# drv592.net
KiCad netlist of a schematic drawn in EAGLE
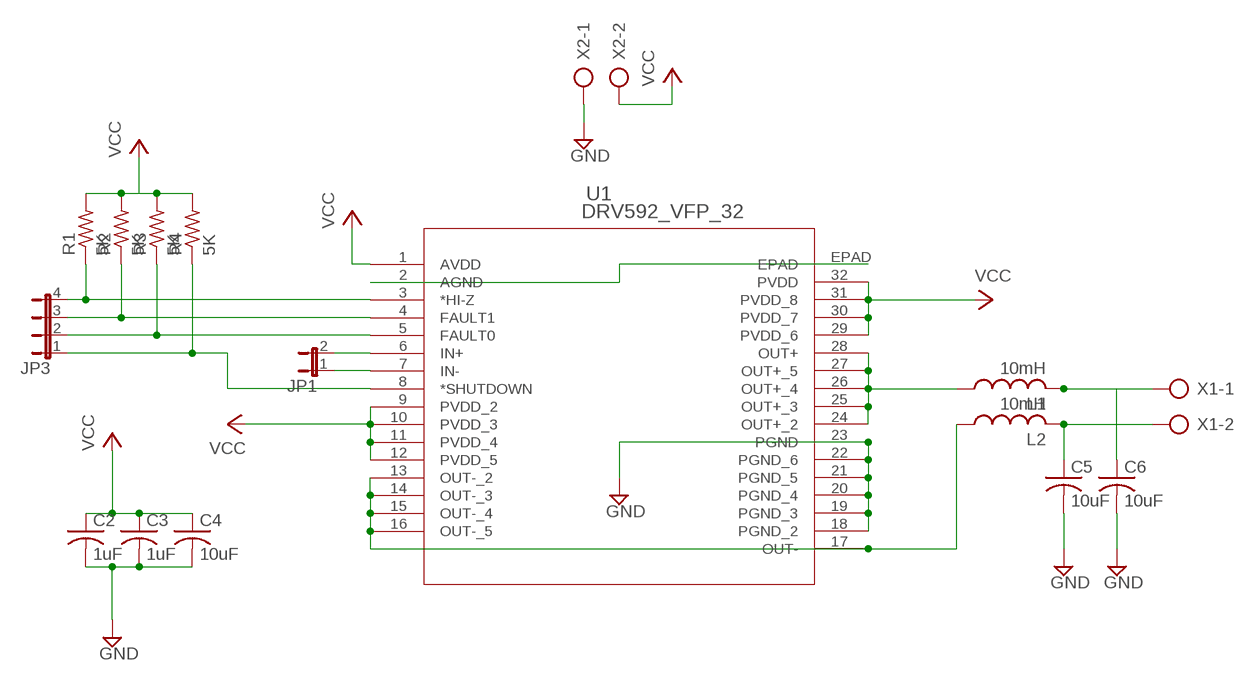
[diagram p0: schematic, sheet 1]

(export (version "E")
  (design (tool "Eeschema 10.0.6"))
  (components
    (comp (ref "C2")
      (value "1uF")
      (footprint "eagle-import:C050-030X075")
      (libsource (lib "eagle-import") (part "C-US050-030X075"))
    )
    (comp (ref "C3")
      (value "1uF")
      (footprint "eagle-import:C050-030X075")
      (libsource (lib "eagle-import") (part "C-US050-030X075"))
    )
    (comp (ref "C4")
      (value "10uF")
      (footprint "eagle-import:C050-030X075")
      (libsource (lib "eagle-import") (part "C-US050-030X075"))
    )
    (comp (ref "C5")
      (value "10uF")
      (footprint "eagle-import:C050-030X075")
      (libsource (lib "eagle-import") (part "C-US050-030X075"))
    )
    (comp (ref "C6")
      (value "10uF")
      (footprint "eagle-import:C050-030X075")
      (libsource (lib "eagle-import") (part "C-US050-030X075"))
    )
    (comp (ref "JP1")
      (value "JP1E")
      (footprint "eagle-import:JP1")
      (libsource (lib "eagle-import") (part "JP1E"))
    )
    (comp (ref "JP3")
      (value "JP4E")
      (footprint "eagle-import:JP4")
      (libsource (lib "eagle-import") (part "JP4E"))
    )
    (comp (ref "L1")
      (value "10mH")
      (footprint "eagle-import:TJ3-U2")
      (libsource (lib "eagle-import") (part "L-USTJ3-U2"))
    )
    (comp (ref "L2")
      (value "10mH")
      (footprint "eagle-import:TJ3-U2")
      (libsource (lib "eagle-import") (part "L-USTJ3-U2"))
    )
    (comp (ref "R1")
      (value "5K")
      (footprint "eagle-import:0207_10")
      (libsource (lib "eagle-import") (part "R-US_0207/10"))
    )
    (comp (ref "R2")
      (value "5K")
      (footprint "eagle-import:0207_10")
      (libsource (lib "eagle-import") (part "R-US_0207/10"))
    )
    (comp (ref "R3")
      (value "5K")
      (footprint "eagle-import:0207_10")
      (libsource (lib "eagle-import") (part "R-US_0207/10"))
    )
    (comp (ref "R4")
      (value "5K")
      (footprint "eagle-import:0207_10")
      (libsource (lib "eagle-import") (part "R-US_0207/10"))
    )
    (comp (ref "U1")
      (value "DRV592_VFP_32")
      (footprint "eagle-import:VFP32_3P91X3P91")
      (fields
        (field (name "GENERIC_PART_NUMBER") "DRV592")
        (field (name "MANUFACTURER") "Texas Instruments")
        (field (name "MANUFACTURER_PART_NUMBER") "drv592_vfp_32")
      )
      (libsource (lib "eagle-import") (part "DRV592_VFP_32"))
    )
    (comp (ref "X1")
      (value "AK300/2")
      (footprint "eagle-import:AK300_2")
      (libsource (lib "eagle-import") (part "AK300/2"))
    )
    (comp (ref "X2")
      (value "AK300/2")
      (footprint "eagle-import:AK300_2")
      (libsource (lib "eagle-import") (part "AK300/2"))
    )
  )
  (nets
    (net (code "1") (name "GND") (class "Default")
      (node (ref "C2") (pin "2") (pinfunction "2_2") (pintype "passive"))
      (node (ref "C3") (pin "2") (pinfunction "2_2") (pintype "passive"))
      (node (ref "C4") (pin "2") (pinfunction "2_2") (pintype "passive"))
      (node (ref "C5") (pin "2") (pinfunction "2_2") (pintype "passive"))
      (node (ref "C6") (pin "2") (pinfunction "2_2") (pintype "passive"))
      (node (ref "U1") (pin "18") (pinfunction "PGND_2_18") (pintype "power_in"))
      (node (ref "U1") (pin "19") (pinfunction "PGND_3_19") (pintype "power_in"))
      (node (ref "U1") (pin "20") (pinfunction "PGND_4_20") (pintype "power_in"))
      (node (ref "U1") (pin "21") (pinfunction "PGND_5_21") (pintype "power_in"))
      (node (ref "U1") (pin "22") (pinfunction "PGND_6_22") (pintype "power_in"))
      (node (ref "U1") (pin "23") (pinfunction "PGND_23") (pintype "power_in"))
      (node (ref "X2") (pin "1") (pinfunction "KL_1") (pintype "passive"))
    )
    (net (code "2") (name "Net-(U1-*HI-Z)") (class "Default")
      (node (ref "JP3") (pin "4") (pinfunction "4_4") (pintype "passive"))
      (node (ref "R1") (pin "1") (pinfunction "1_1") (pintype "passive"))
      (node (ref "U1") (pin "3") (pinfunction "*HI-Z_3") (pintype "input"))
    )
    (net (code "3") (name "Net-(U1-*SHUTDOWN)") (class "Default")
      (node (ref "JP3") (pin "1") (pinfunction "1_1") (pintype "passive"))
      (node (ref "R4") (pin "1") (pinfunction "1_1") (pintype "passive"))
      (node (ref "U1") (pin "8") (pinfunction "*SHUTDOWN_8") (pintype "input"))
    )
    (net (code "4") (name "Net-(U1-AGND)") (class "Default")
      (node (ref "U1") (pin "2") (pinfunction "AGND_2") (pintype "power_in"))
      (node (ref "U1") (pin "EPAD") (pinfunction "EPAD_EPAD") (pintype "passive"))
    )
    (net (code "5") (name "Net-(U1-FAULT0)") (class "Default")
      (node (ref "JP3") (pin "2") (pinfunction "2_2") (pintype "passive"))
      (node (ref "R3") (pin "1") (pinfunction "1_1") (pintype "passive"))
      (node (ref "U1") (pin "5") (pinfunction "FAULT0_5") (pintype "output"))
    )
    (net (code "6") (name "Net-(U1-FAULT1)") (class "Default")
      (node (ref "JP3") (pin "3") (pinfunction "3_3") (pintype "passive"))
      (node (ref "R2") (pin "1") (pinfunction "1_1") (pintype "passive"))
      (node (ref "U1") (pin "4") (pinfunction "FAULT1_4") (pintype "output"))
    )
    (net (code "7") (name "Net-(U1-IN+)") (class "Default")
      (node (ref "JP1") (pin "2") (pinfunction "2_2") (pintype "passive"))
      (node (ref "U1") (pin "6") (pinfunction "IN+_6") (pintype "input"))
    )
    (net (code "8") (name "Net-(U1-IN-)") (class "Default")
      (node (ref "JP1") (pin "1") (pinfunction "1_1") (pintype "passive"))
      (node (ref "U1") (pin "7") (pinfunction "IN-_7") (pintype "input"))
    )
    (net (code "9") (name "Net-(U1-OUT+)") (class "Default")
      (node (ref "L1") (pin "1") (pinfunction "1_1") (pintype "passive"))
      (node (ref "U1") (pin "24") (pinfunction "OUT+_2_24") (pintype "output"))
      (node (ref "U1") (pin "25") (pinfunction "OUT+_3_25") (pintype "output"))
      (node (ref "U1") (pin "26") (pinfunction "OUT+_4_26") (pintype "output"))
      (node (ref "U1") (pin "27") (pinfunction "OUT+_5_27") (pintype "output"))
      (node (ref "U1") (pin "28") (pinfunction "OUT+_28") (pintype "output"))
    )
    (net (code "10") (name "Net-(U1-OUT-)") (class "Default")
      (node (ref "L2") (pin "1") (pinfunction "1_1") (pintype "passive"))
      (node (ref "U1") (pin "13") (pinfunction "OUT-_2_13") (pintype "output"))
      (node (ref "U1") (pin "14") (pinfunction "OUT-_3_14") (pintype "output"))
      (node (ref "U1") (pin "15") (pinfunction "OUT-_4_15") (pintype "output"))
      (node (ref "U1") (pin "16") (pinfunction "OUT-_5_16") (pintype "output"))
      (node (ref "U1") (pin "17") (pinfunction "OUT-_17") (pintype "output"))
    )
    (net (code "11") (name "Net-(X1A-KL)") (class "Default")
      (node (ref "C6") (pin "1") (pinfunction "1_1") (pintype "passive"))
      (node (ref "L1") (pin "2") (pinfunction "2_2") (pintype "passive"))
      (node (ref "X1") (pin "1") (pinfunction "KL_1") (pintype "passive"))
    )
    (net (code "12") (name "Net-(X1B-KL)") (class "Default")
      (node (ref "C5") (pin "1") (pinfunction "1_1") (pintype "passive"))
      (node (ref "L2") (pin "2") (pinfunction "2_2") (pintype "passive"))
      (node (ref "X1") (pin "2") (pinfunction "KL_2") (pintype "passive"))
    )
    (net (code "13") (name "VCC") (class "Default")
      (node (ref "C2") (pin "1") (pinfunction "1_1") (pintype "passive"))
      (node (ref "C3") (pin "1") (pinfunction "1_1") (pintype "passive"))
      (node (ref "C4") (pin "1") (pinfunction "1_1") (pintype "passive"))
      (node (ref "R1") (pin "2") (pinfunction "2_2") (pintype "passive"))
      (node (ref "R2") (pin "2") (pinfunction "2_2") (pintype "passive"))
      (node (ref "R3") (pin "2") (pinfunction "2_2") (pintype "passive"))
      (node (ref "R4") (pin "2") (pinfunction "2_2") (pintype "passive"))
      (node (ref "U1") (pin "1") (pinfunction "AVDD_1") (pintype "power_in"))
      (node (ref "U1") (pin "10") (pinfunction "PVDD_3_10") (pintype "power_in"))
      (node (ref "U1") (pin "11") (pinfunction "PVDD_4_11") (pintype "power_in"))
      (node (ref "U1") (pin "12") (pinfunction "PVDD_5_12") (pintype "power_in"))
      (node (ref "U1") (pin "29") (pinfunction "PVDD_6_29") (pintype "power_in"))
      (node (ref "U1") (pin "30") (pinfunction "PVDD_7_30") (pintype "power_in"))
      (node (ref "U1") (pin "31") (pinfunction "PVDD_8_31") (pintype "power_in"))
      (node (ref "U1") (pin "32") (pinfunction "PVDD_32") (pintype "power_in"))
      (node (ref "U1") (pin "9") (pinfunction "PVDD_2_9") (pintype "power_in"))
      (node (ref "X2") (pin "2") (pinfunction "KL_2") (pintype "passive"))
    )
  )
)
